# Generic_555_Astable.net
KiCad netlist of a schematic drawn in Altium Designer
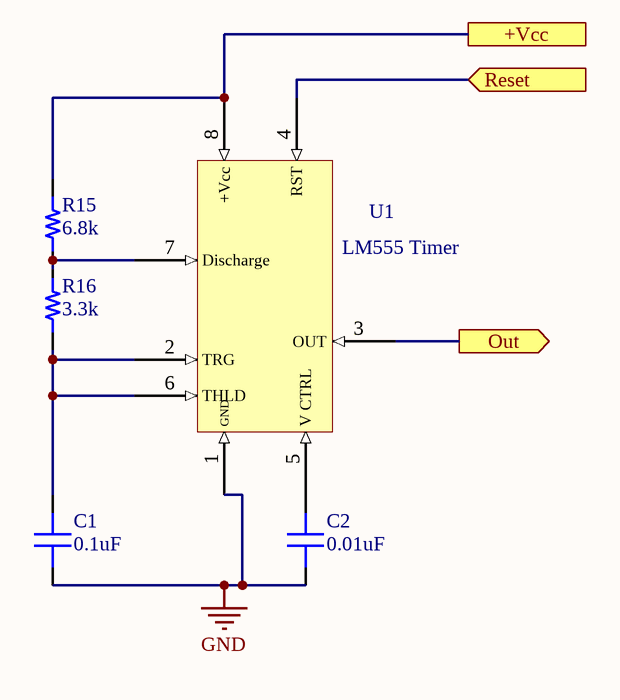
[diagram p0: Generic_555_Astable.SchDoc]

(export (version "E")
  (design (tool "Eeschema 10.0.6"))
  (components
    (comp (ref "C1")
      (value "capacitor")
      (footprint "0603")
      (description "Generic 0603 capacitor")
      (fields (field (name "CAPACITANCE") "0.1uF") (field (name "VOLTAGE") "50"))
      (libsource (lib "altlib") (part "capacitor"))
    )
    (comp (ref "C2")
      (value "capacitor")
      (footprint "0603")
      (description "Generic 0603 capacitor")
      (fields (field (name "CAPACITANCE") "0.01uF") (field (name "VOLTAGE") "50"))
      (libsource (lib "altlib") (part "capacitor"))
    )
    (comp (ref "R15")
      (value "6.8k")
      (footprint "RES 0603/1608")
      (fields (field (name "RESISTANCE") "6.8k"))
      (libsource (lib "altlib") (part "Resistor"))
    )
    (comp (ref "R16")
      (value "3.3k")
      (footprint "RES 0603/1608")
      (fields (field (name "RESISTANCE") "3.3k"))
      (libsource (lib "altlib") (part "Resistor"))
    )
    (comp (ref "U1")
      (value "LM555 Timer")
      (footprint "SOIC-8")
      (libsource (lib "altlib") (part "LM555 Timer"))
    )
  )
  (nets
    (net (code "1") (name "/+Vcc") (class "Default")
      (node (ref "R15") (pin "2") (pinfunction "2_2") (pintype "passive"))
      (node (ref "U1") (pin "8") (pinfunction "+Vcc_8") (pintype "input"))
    )
    (net (code "2") (name "/Out") (class "Default")
      (node (ref "U1") (pin "3") (pinfunction "OUT_3") (pintype "input"))
    )
    (net (code "3") (name "/Reset") (class "Default")
      (node (ref "U1") (pin "4") (pinfunction "RST_4") (pintype "input"))
    )
    (net (code "4") (name "GND") (class "Default")
      (node (ref "C1") (pin "1") (pinfunction "1_1") (pintype "passive"))
      (node (ref "C2") (pin "1") (pinfunction "1_1") (pintype "passive"))
      (node (ref "U1") (pin "1") (pinfunction "GND_1") (pintype "input"))
    )
    (net (code "5") (name "Net-(U1-Discharge)") (class "Default")
      (node (ref "R15") (pin "1") (pinfunction "1_1") (pintype "passive"))
      (node (ref "R16") (pin "2") (pinfunction "2_2") (pintype "passive"))
      (node (ref "U1") (pin "7") (pinfunction "Discharge_7") (pintype "input"))
    )
    (net (code "6") (name "Net-(U1-THLD)") (class "Default")
      (node (ref "C1") (pin "2") (pinfunction "2_2") (pintype "passive"))
      (node (ref "R16") (pin "1") (pinfunction "1_1") (pintype "passive"))
      (node (ref "U1") (pin "2") (pinfunction "TRG_2") (pintype "input"))
      (node (ref "U1") (pin "6") (pinfunction "THLD_6") (pintype "input"))
    )
    (net (code "7") (name "Net-(U1-V_CTRL)") (class "Default")
      (node (ref "C2") (pin "2") (pinfunction "2_2") (pintype "passive"))
      (node (ref "U1") (pin "5") (pinfunction "V_CTRL_5") (pintype "input"))
    )
  )
)
